# 16F716DHT11.net
KiCad netlist of a schematic drawn in EAGLE
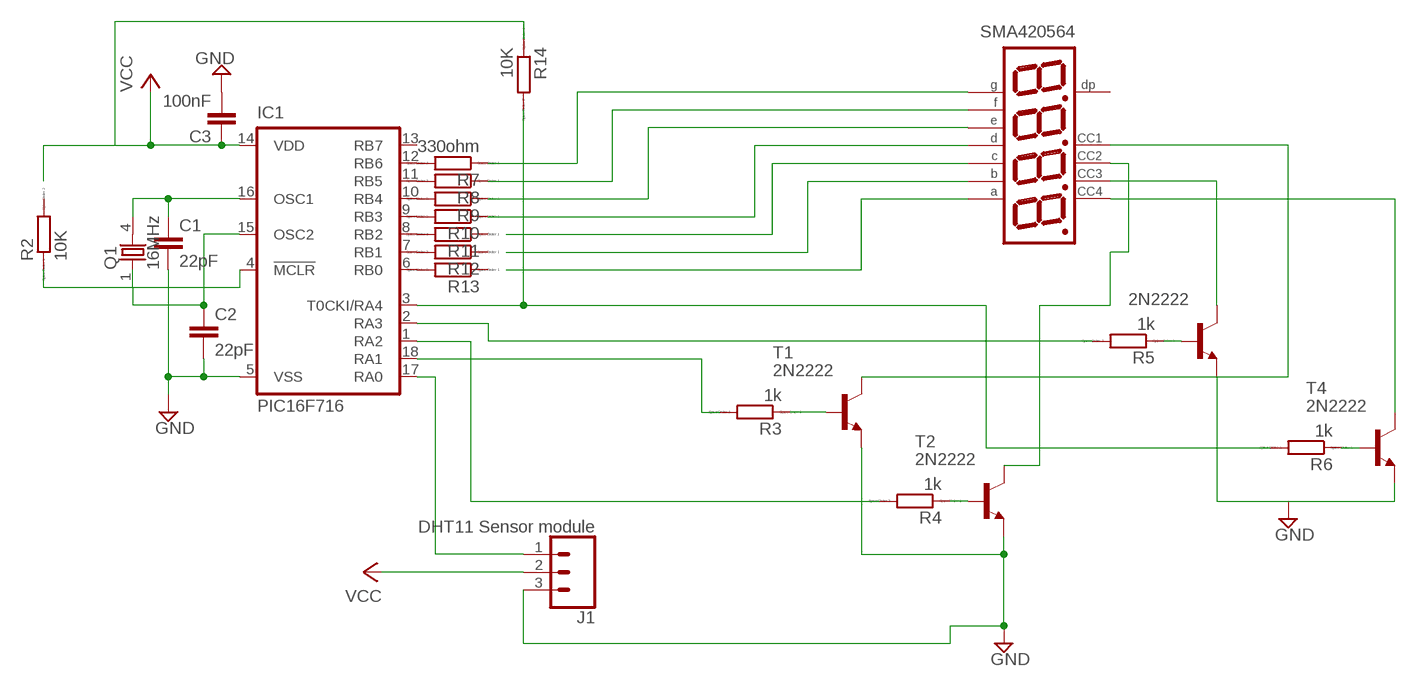
[diagram p0: schematic, sheet 1]

(export (version "E")
  (design (tool "Eeschema 10.0.6"))
  (components
    (comp (ref "C1")
      (value "22pF")
      (footprint "eagle-import:C2.5-3")
      (libsource (lib "eagle-import") (part "C2,5-3"))
    )
    (comp (ref "C2")
      (value "22pF")
      (footprint "eagle-import:C2.5-3")
      (libsource (lib "eagle-import") (part "C2,5-3"))
    )
    (comp (ref "C3")
      (value "100nF")
      (footprint "eagle-import:C2.5-3")
      (libsource (lib "eagle-import") (part "C2,5-3"))
    )
    (comp (ref "IC1")
      (value "PIC16F716")
      (footprint "eagle-import:DIL18")
      (libsource (lib "eagle-import") (part "PIC16F8P3"))
    )
    (comp (ref "J1")
      (value "DHT11 Sensor module")
      (footprint "eagle-import:1X03")
      (libsource (lib "eagle-import") (part "CONN_03"))
    )
    (comp (ref "Q1")
      (value "16MHz")
      (footprint "eagle-import:86SMX")
      (fields (field (name "MF") "C-MAC  FREQUENCY PRODUCTS LTD") (field (name "MPN") "XTAL003321- 86SMX"))
      (libsource (lib "eagle-import") (part "86SMX"))
    )
    (comp (ref "R2")
      (value "10K")
      (footprint "eagle-import:0204_7")
      (libsource (lib "eagle-import") (part "R0204/7"))
    )
    (comp (ref "R3")
      (value "1k")
      (footprint "eagle-import:0204_7")
      (libsource (lib "eagle-import") (part "R0204/7"))
    )
    (comp (ref "R4")
      (value "1k")
      (footprint "eagle-import:0204_7")
      (libsource (lib "eagle-import") (part "R0204/7"))
    )
    (comp (ref "R5")
      (value "1k")
      (footprint "eagle-import:0204_7")
      (libsource (lib "eagle-import") (part "R0204/7"))
    )
    (comp (ref "R6")
      (value "1k")
      (footprint "eagle-import:0204_7")
      (libsource (lib "eagle-import") (part "R0204/7"))
    )
    (comp (ref "R7")
      (value "330ohm")
      (footprint "eagle-import:0204_7")
      (libsource (lib "eagle-import") (part "R0204/7"))
    )
    (comp (ref "R8")
      (value "R0204/7")
      (footprint "eagle-import:0204_7")
      (libsource (lib "eagle-import") (part "R0204/7"))
    )
    (comp (ref "R9")
      (value "R0204/7")
      (footprint "eagle-import:0204_7")
      (libsource (lib "eagle-import") (part "R0204/7"))
    )
    (comp (ref "R10")
      (value "R0204/7")
      (footprint "eagle-import:0204_7")
      (libsource (lib "eagle-import") (part "R0204/7"))
    )
    (comp (ref "R11")
      (value "R0204/7")
      (footprint "eagle-import:0204_7")
      (libsource (lib "eagle-import") (part "R0204/7"))
    )
    (comp (ref "R12")
      (value "R0204/7")
      (footprint "eagle-import:0204_7")
      (libsource (lib "eagle-import") (part "R0204/7"))
    )
    (comp (ref "R13")
      (value "R0204/7")
      (footprint "eagle-import:0204_7")
      (libsource (lib "eagle-import") (part "R0204/7"))
    )
    (comp (ref "R14")
      (value "10K")
      (footprint "eagle-import:0204_7")
      (libsource (lib "eagle-import") (part "R0204/7"))
    )
    (comp (ref "SMA420564")
      (value "NFD-5641AS")
      (footprint "eagle-import:NFD-5641")
      (libsource (lib "eagle-import") (part "NFD-5641AS"))
    )
    (comp (ref "T1")
      (value "2N2222")
      (footprint "eagle-import:TO18")
      (libsource (lib "eagle-import") (part "2N2222"))
    )
    (comp (ref "T2")
      (value "2N2222")
      (footprint "eagle-import:TO18")
      (libsource (lib "eagle-import") (part "2N2222"))
    )
    (comp (ref "T3")
      (value "2N2222")
      (footprint "eagle-import:TO18")
      (libsource (lib "eagle-import") (part "2N2222"))
    )
    (comp (ref "T4")
      (value "2N2222")
      (footprint "eagle-import:TO18")
      (libsource (lib "eagle-import") (part "2N2222"))
    )
  )
  (nets
    (net (code "1") (name "GND") (class "Default")
      (node (ref "C1") (pin "2") (pinfunction "2_2") (pintype "passive"))
      (node (ref "C2") (pin "2") (pinfunction "2_2") (pintype "passive"))
      (node (ref "C3") (pin "2") (pinfunction "2_2") (pintype "passive"))
      (node (ref "IC1") (pin "5") (pinfunction "VSS_5") (pintype "power_in"))
      (node (ref "J1") (pin "3") (pinfunction "3_3") (pintype "passive"))
      (node (ref "T1") (pin "1") (pinfunction "E_1") (pintype "passive"))
      (node (ref "T2") (pin "1") (pinfunction "E_1") (pintype "passive"))
      (node (ref "T3") (pin "1") (pinfunction "E_1") (pintype "passive"))
      (node (ref "T4") (pin "1") (pinfunction "E_1") (pintype "passive"))
    )
    (net (code "2") (name "Net-(IC1-OSC1)") (class "Default")
      (node (ref "C1") (pin "1") (pinfunction "1_1") (pintype "passive"))
      (node (ref "IC1") (pin "16") (pinfunction "OSC1_16") (pintype "input"))
      (node (ref "Q1") (pin "4") (pinfunction "2_4") (pintype "passive"))
    )
    (net (code "3") (name "Net-(IC1-OSC2)") (class "Default")
      (node (ref "C2") (pin "1") (pinfunction "1_1") (pintype "passive"))
      (node (ref "IC1") (pin "15") (pinfunction "OSC2_15") (pintype "output"))
      (node (ref "Q1") (pin "1") (pinfunction "1_1") (pintype "passive"))
    )
    (net (code "4") (name "Net-(IC1-RA0)") (class "Default")
      (node (ref "IC1") (pin "17") (pinfunction "RA0_17") (pintype "bidirectional"))
      (node (ref "J1") (pin "1") (pinfunction "1_1") (pintype "passive"))
    )
    (net (code "5") (name "Net-(IC1-RA1)") (class "Default")
      (node (ref "IC1") (pin "18") (pinfunction "RA1_18") (pintype "bidirectional"))
      (node (ref "R3") (pin "2") (pinfunction "2_2") (pintype "passive"))
    )
    (net (code "6") (name "Net-(IC1-RA2)") (class "Default")
      (node (ref "IC1") (pin "1") (pinfunction "RA2_1") (pintype "bidirectional"))
      (node (ref "R4") (pin "2") (pinfunction "2_2") (pintype "passive"))
    )
    (net (code "7") (name "Net-(IC1-RA3)") (class "Default")
      (node (ref "IC1") (pin "2") (pinfunction "RA3_2") (pintype "bidirectional"))
      (node (ref "R5") (pin "2") (pinfunction "2_2") (pintype "passive"))
    )
    (net (code "8") (name "Net-(IC1-RB0)") (class "Default")
      (node (ref "IC1") (pin "6") (pinfunction "RB0_6") (pintype "bidirectional"))
      (node (ref "R13") (pin "2") (pinfunction "2_2") (pintype "passive"))
    )
    (net (code "9") (name "Net-(IC1-RB1)") (class "Default")
      (node (ref "IC1") (pin "7") (pinfunction "RB1_7") (pintype "bidirectional"))
      (node (ref "R12") (pin "2") (pinfunction "2_2") (pintype "passive"))
    )
    (net (code "10") (name "Net-(IC1-RB2)") (class "Default")
      (node (ref "IC1") (pin "8") (pinfunction "RB2_8") (pintype "bidirectional"))
      (node (ref "R11") (pin "2") (pinfunction "2_2") (pintype "passive"))
    )
    (net (code "11") (name "Net-(IC1-RB3)") (class "Default")
      (node (ref "IC1") (pin "9") (pinfunction "RB3_9") (pintype "bidirectional"))
      (node (ref "R10") (pin "2") (pinfunction "2_2") (pintype "passive"))
    )
    (net (code "12") (name "Net-(IC1-RB4)") (class "Default")
      (node (ref "IC1") (pin "10") (pinfunction "RB4_10") (pintype "bidirectional"))
      (node (ref "R9") (pin "2") (pinfunction "2_2") (pintype "passive"))
    )
    (net (code "13") (name "Net-(IC1-RB5)") (class "Default")
      (node (ref "IC1") (pin "11") (pinfunction "RB5_11") (pintype "bidirectional"))
      (node (ref "R8") (pin "2") (pinfunction "2_2") (pintype "passive"))
    )
    (net (code "14") (name "Net-(IC1-RB6)") (class "Default")
      (node (ref "IC1") (pin "12") (pinfunction "RB6_12") (pintype "bidirectional"))
      (node (ref "R7") (pin "2") (pinfunction "2_2") (pintype "passive"))
    )
    (net (code "15") (name "Net-(IC1-T0CKI{slash}RA4)") (class "Default")
      (node (ref "IC1") (pin "3") (pinfunction "T0CKI/RA4_3") (pintype "bidirectional"))
      (node (ref "R14") (pin "2") (pinfunction "2_2") (pintype "passive"))
      (node (ref "R6") (pin "2") (pinfunction "2_2") (pintype "passive"))
    )
    (net (code "16") (name "Net-(IC1-~{MCLR})") (class "Default")
      (node (ref "IC1") (pin "4") (pinfunction "~{MCLR}_4") (pintype "input"))
      (node (ref "R2") (pin "1") (pinfunction "1_1") (pintype "passive"))
    )
    (net (code "17") (name "Net-(R7-Pad1)") (class "Default")
      (node (ref "R7") (pin "1") (pinfunction "1_1") (pintype "passive"))
      (node (ref "SMA420564") (pin "P$5") (pinfunction "P$5_P$5") (pintype "bidirectional"))
    )
    (net (code "18") (name "Net-(R8-Pad1)") (class "Default")
      (node (ref "R8") (pin "1") (pinfunction "1_1") (pintype "passive"))
      (node (ref "SMA420564") (pin "P$10") (pinfunction "P$10_P$10") (pintype "bidirectional"))
    )
    (net (code "19") (name "Net-(R9-Pad1)") (class "Default")
      (node (ref "R9") (pin "1") (pinfunction "1_1") (pintype "passive"))
      (node (ref "SMA420564") (pin "P$1") (pinfunction "P$1_P$1") (pintype "bidirectional"))
    )
    (net (code "20") (name "Net-(R10-Pad1)") (class "Default")
      (node (ref "R10") (pin "1") (pinfunction "1_1") (pintype "passive"))
      (node (ref "SMA420564") (pin "P$2") (pinfunction "P$2_P$2") (pintype "bidirectional"))
    )
    (net (code "21") (name "Net-(T1-B)") (class "Default")
      (node (ref "R3") (pin "1") (pinfunction "1_1") (pintype "passive"))
      (node (ref "T1") (pin "2") (pinfunction "B_2") (pintype "passive"))
    )
    (net (code "22") (name "Net-(T1-C)") (class "Default")
      (node (ref "SMA420564") (pin "P$12") (pinfunction "P$12_P$12") (pintype "bidirectional"))
      (node (ref "T1") (pin "3") (pinfunction "C_3") (pintype "passive"))
    )
    (net (code "23") (name "Net-(T2-B)") (class "Default")
      (node (ref "R4") (pin "1") (pinfunction "1_1") (pintype "passive"))
      (node (ref "T2") (pin "2") (pinfunction "B_2") (pintype "passive"))
    )
    (net (code "24") (name "Net-(T2-C)") (class "Default")
      (node (ref "SMA420564") (pin "P$9") (pinfunction "P$9_P$9") (pintype "bidirectional"))
      (node (ref "T2") (pin "3") (pinfunction "C_3") (pintype "passive"))
    )
    (net (code "25") (name "Net-(T3-B)") (class "Default")
      (node (ref "R5") (pin "1") (pinfunction "1_1") (pintype "passive"))
      (node (ref "T3") (pin "2") (pinfunction "B_2") (pintype "passive"))
    )
    (net (code "26") (name "Net-(T3-C)") (class "Default")
      (node (ref "SMA420564") (pin "P$8") (pinfunction "P$8_P$8") (pintype "bidirectional"))
      (node (ref "T3") (pin "3") (pinfunction "C_3") (pintype "passive"))
    )
    (net (code "27") (name "Net-(T4-B)") (class "Default")
      (node (ref "R6") (pin "1") (pinfunction "1_1") (pintype "passive"))
      (node (ref "T4") (pin "2") (pinfunction "B_2") (pintype "passive"))
    )
    (net (code "28") (name "Net-(T4-C)") (class "Default")
      (node (ref "SMA420564") (pin "P$6") (pinfunction "P$6_P$6") (pintype "bidirectional"))
      (node (ref "T4") (pin "3") (pinfunction "C_3") (pintype "passive"))
    )
    (net (code "29") (name "VCC") (class "Default")
      (node (ref "C3") (pin "1") (pinfunction "1_1") (pintype "passive"))
      (node (ref "IC1") (pin "14") (pinfunction "VDD_14") (pintype "power_in"))
      (node (ref "J1") (pin "2") (pinfunction "2_2") (pintype "passive"))
      (node (ref "R14") (pin "1") (pinfunction "1_1") (pintype "passive"))
    )
    (net (code "30") (name "unconnected-(IC1-RB7-Pad13)") (class "Default")
      (node (ref "IC1") (pin "13") (pinfunction "RB7_13") (pintype "bidirectional"))
    )
    (net (code "31") (name "unconnected-(R2-Pad2)") (class "Default")
      (node (ref "R2") (pin "2") (pinfunction "2_2") (pintype "passive"))
    )
    (net (code "32") (name "unconnected-(R11-Pad1)") (class "Default")
      (node (ref "R11") (pin "1") (pinfunction "1_1") (pintype "passive"))
    )
    (net (code "33") (name "unconnected-(R12-Pad1)") (class "Default")
      (node (ref "R12") (pin "1") (pinfunction "1_1") (pintype "passive"))
    )
    (net (code "34") (name "unconnected-(R13-Pad1)") (class "Default")
      (node (ref "R13") (pin "1") (pinfunction "1_1") (pintype "passive"))
    )
    (net (code "35") (name "unconnected-(SMA420564-PadP$3)") (class "Default")
      (node (ref "SMA420564") (pin "P$3") (pinfunction "P$3_P$3") (pintype "bidirectional"))
    )
    (net (code "36") (name "unconnected-(SMA420564-PadP$4)") (class "Default")
      (node (ref "SMA420564") (pin "P$4") (pinfunction "P$4_P$4") (pintype "bidirectional"))
    )
    (net (code "37") (name "unconnected-(SMA420564-PadP$7)") (class "Default")
      (node (ref "SMA420564") (pin "P$7") (pinfunction "P$7_P$7") (pintype "bidirectional"))
    )
    (net (code "38") (name "unconnected-(SMA420564-PadP$11)") (class "Default")
      (node (ref "SMA420564") (pin "P$11") (pinfunction "P$11_P$11") (pintype "bidirectional"))
    )
  )
)
